# TESTPL.net
KiCad netlist of a schematic drawn in EAGLE
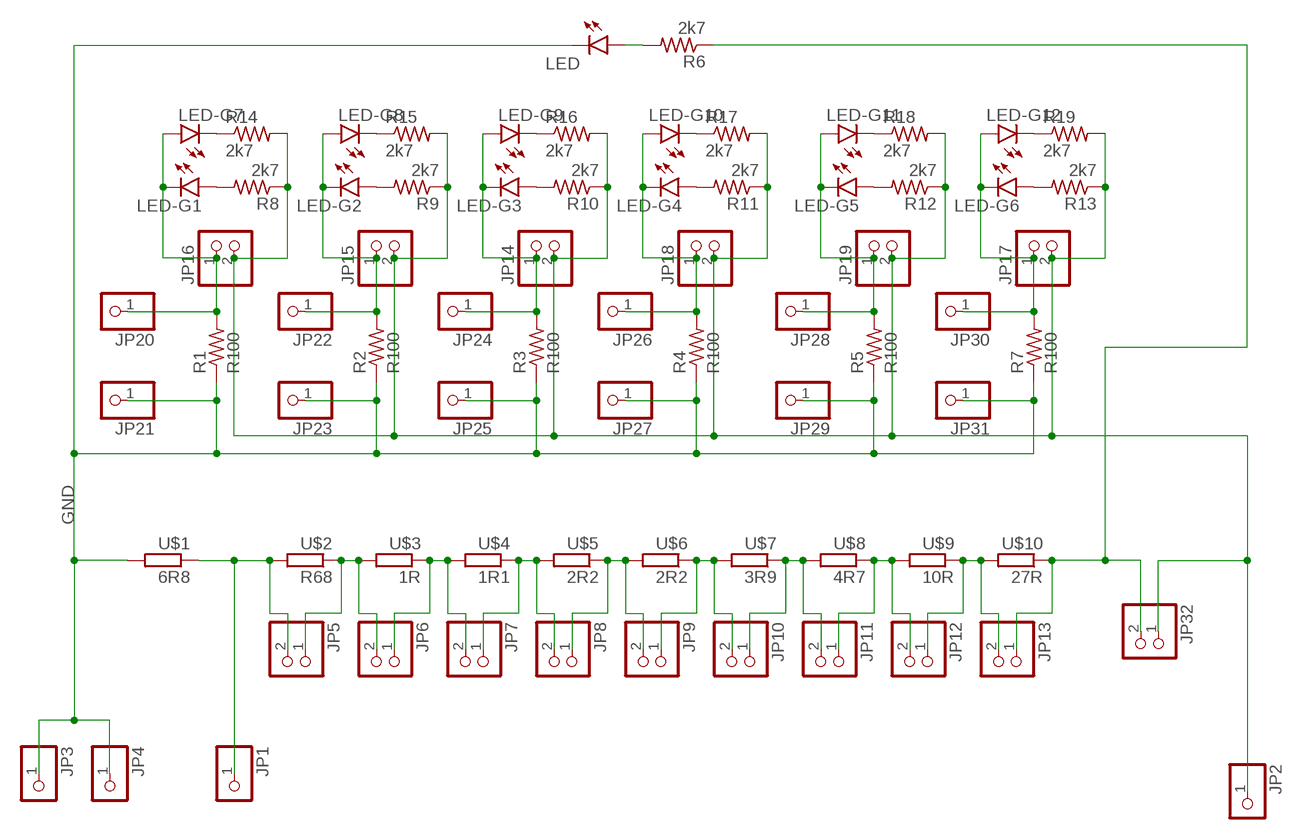
[diagram p0: schematic, sheet 1]

(export (version "E")
  (design (tool "Eeschema 10.0.6"))
  (components
    (comp (ref "JP1")
      (value "PINHD-1X1")
      (footprint "eagle-import:1X01")
      (libsource (lib "eagle-import") (part "PINHD-1X1"))
    )
    (comp (ref "JP2")
      (value "PINHD-1X1")
      (footprint "eagle-import:1X01")
      (libsource (lib "eagle-import") (part "PINHD-1X1"))
    )
    (comp (ref "JP3")
      (value "PINHD-1X1")
      (footprint "eagle-import:1X01")
      (libsource (lib "eagle-import") (part "PINHD-1X1"))
    )
    (comp (ref "JP4")
      (value "PINHD-1X1")
      (footprint "eagle-import:1X01")
      (libsource (lib "eagle-import") (part "PINHD-1X1"))
    )
    (comp (ref "JP5")
      (value "PINHD-1X2")
      (footprint "eagle-import:1X02")
      (libsource (lib "eagle-import") (part "PINHD-1X2"))
    )
    (comp (ref "JP6")
      (value "PINHD-1X2")
      (footprint "eagle-import:1X02")
      (libsource (lib "eagle-import") (part "PINHD-1X2"))
    )
    (comp (ref "JP7")
      (value "PINHD-1X2")
      (footprint "eagle-import:1X02")
      (libsource (lib "eagle-import") (part "PINHD-1X2"))
    )
    (comp (ref "JP8")
      (value "PINHD-1X2")
      (footprint "eagle-import:1X02")
      (libsource (lib "eagle-import") (part "PINHD-1X2"))
    )
    (comp (ref "JP9")
      (value "PINHD-1X2")
      (footprint "eagle-import:1X02")
      (libsource (lib "eagle-import") (part "PINHD-1X2"))
    )
    (comp (ref "JP10")
      (value "PINHD-1X2")
      (footprint "eagle-import:1X02")
      (libsource (lib "eagle-import") (part "PINHD-1X2"))
    )
    (comp (ref "JP11")
      (value "PINHD-1X2")
      (footprint "eagle-import:1X02")
      (libsource (lib "eagle-import") (part "PINHD-1X2"))
    )
    (comp (ref "JP12")
      (value "PINHD-1X2")
      (footprint "eagle-import:1X02")
      (libsource (lib "eagle-import") (part "PINHD-1X2"))
    )
    (comp (ref "JP13")
      (value "PINHD-1X2")
      (footprint "eagle-import:1X02")
      (libsource (lib "eagle-import") (part "PINHD-1X2"))
    )
    (comp (ref "JP14")
      (value "PINHD-1X2")
      (footprint "eagle-import:1X02")
      (libsource (lib "eagle-import") (part "PINHD-1X2"))
    )
    (comp (ref "JP15")
      (value "PINHD-1X2")
      (footprint "eagle-import:1X02")
      (libsource (lib "eagle-import") (part "PINHD-1X2"))
    )
    (comp (ref "JP16")
      (value "PINHD-1X2")
      (footprint "eagle-import:1X02")
      (libsource (lib "eagle-import") (part "PINHD-1X2"))
    )
    (comp (ref "JP17")
      (value "PINHD-1X2")
      (footprint "eagle-import:1X02")
      (libsource (lib "eagle-import") (part "PINHD-1X2"))
    )
    (comp (ref "JP18")
      (value "PINHD-1X2")
      (footprint "eagle-import:1X02")
      (libsource (lib "eagle-import") (part "PINHD-1X2"))
    )
    (comp (ref "JP19")
      (value "PINHD-1X2")
      (footprint "eagle-import:1X02")
      (libsource (lib "eagle-import") (part "PINHD-1X2"))
    )
    (comp (ref "JP20")
      (value "PINHD-1X1")
      (footprint "eagle-import:1X01")
      (libsource (lib "eagle-import") (part "PINHD-1X1"))
    )
    (comp (ref "JP21")
      (value "PINHD-1X1")
      (footprint "eagle-import:1X01")
      (libsource (lib "eagle-import") (part "PINHD-1X1"))
    )
    (comp (ref "JP22")
      (value "PINHD-1X1")
      (footprint "eagle-import:1X01")
      (libsource (lib "eagle-import") (part "PINHD-1X1"))
    )
    (comp (ref "JP23")
      (value "PINHD-1X1")
      (footprint "eagle-import:1X01")
      (libsource (lib "eagle-import") (part "PINHD-1X1"))
    )
    (comp (ref "JP24")
      (value "PINHD-1X1")
      (footprint "eagle-import:1X01")
      (libsource (lib "eagle-import") (part "PINHD-1X1"))
    )
    (comp (ref "JP25")
      (value "PINHD-1X1")
      (footprint "eagle-import:1X01")
      (libsource (lib "eagle-import") (part "PINHD-1X1"))
    )
    (comp (ref "JP26")
      (value "PINHD-1X1")
      (footprint "eagle-import:1X01")
      (libsource (lib "eagle-import") (part "PINHD-1X1"))
    )
    (comp (ref "JP27")
      (value "PINHD-1X1")
      (footprint "eagle-import:1X01")
      (libsource (lib "eagle-import") (part "PINHD-1X1"))
    )
    (comp (ref "JP28")
      (value "PINHD-1X1")
      (footprint "eagle-import:1X01")
      (libsource (lib "eagle-import") (part "PINHD-1X1"))
    )
    (comp (ref "JP29")
      (value "PINHD-1X1")
      (footprint "eagle-import:1X01")
      (libsource (lib "eagle-import") (part "PINHD-1X1"))
    )
    (comp (ref "JP30")
      (value "PINHD-1X1")
      (footprint "eagle-import:1X01")
      (libsource (lib "eagle-import") (part "PINHD-1X1"))
    )
    (comp (ref "JP31")
      (value "PINHD-1X1")
      (footprint "eagle-import:1X01")
      (libsource (lib "eagle-import") (part "PINHD-1X1"))
    )
    (comp (ref "JP32")
      (value "PINHD-1X2")
      (footprint "eagle-import:1X02")
      (libsource (lib "eagle-import") (part "PINHD-1X2"))
    )
    (comp (ref "LED")
      (value "LEDCHIPLED_0603")
      (footprint "eagle-import:CHIPLED_0603")
      (libsource (lib "eagle-import") (part "LEDCHIPLED_0603"))
    )
    (comp (ref "LED-G1")
      (value "LEDCHIPLED_0603")
      (footprint "eagle-import:CHIPLED_0603")
      (libsource (lib "eagle-import") (part "LEDCHIPLED_0603"))
    )
    (comp (ref "LED-G2")
      (value "LEDCHIPLED_0603")
      (footprint "eagle-import:CHIPLED_0603")
      (libsource (lib "eagle-import") (part "LEDCHIPLED_0603"))
    )
    (comp (ref "LED-G3")
      (value "LEDCHIPLED_0603")
      (footprint "eagle-import:CHIPLED_0603")
      (libsource (lib "eagle-import") (part "LEDCHIPLED_0603"))
    )
    (comp (ref "LED-G4")
      (value "LEDCHIPLED_0603")
      (footprint "eagle-import:CHIPLED_0603")
      (libsource (lib "eagle-import") (part "LEDCHIPLED_0603"))
    )
    (comp (ref "LED-G5")
      (value "LEDCHIPLED_0603")
      (footprint "eagle-import:CHIPLED_0603")
      (libsource (lib "eagle-import") (part "LEDCHIPLED_0603"))
    )
    (comp (ref "LED-G6")
      (value "LEDCHIPLED_0603")
      (footprint "eagle-import:CHIPLED_0603")
      (libsource (lib "eagle-import") (part "LEDCHIPLED_0603"))
    )
    (comp (ref "LED-G7")
      (value "LEDCHIPLED_0603")
      (footprint "eagle-import:CHIPLED_0603")
      (libsource (lib "eagle-import") (part "LEDCHIPLED_0603"))
    )
    (comp (ref "LED-G8")
      (value "LEDCHIPLED_0603")
      (footprint "eagle-import:CHIPLED_0603")
      (libsource (lib "eagle-import") (part "LEDCHIPLED_0603"))
    )
    (comp (ref "LED-G9")
      (value "LEDCHIPLED_0603")
      (footprint "eagle-import:CHIPLED_0603")
      (libsource (lib "eagle-import") (part "LEDCHIPLED_0603"))
    )
    (comp (ref "LED-G10")
      (value "LEDCHIPLED_0603")
      (footprint "eagle-import:CHIPLED_0603")
      (libsource (lib "eagle-import") (part "LEDCHIPLED_0603"))
    )
    (comp (ref "LED-G11")
      (value "LEDCHIPLED_0603")
      (footprint "eagle-import:CHIPLED_0603")
      (libsource (lib "eagle-import") (part "LEDCHIPLED_0603"))
    )
    (comp (ref "LED-G12")
      (value "LEDCHIPLED_0603")
      (footprint "eagle-import:CHIPLED_0603")
      (libsource (lib "eagle-import") (part "LEDCHIPLED_0603"))
    )
    (comp (ref "R1")
      (value "R100")
      (footprint "eagle-import:R2512")
      (libsource (lib "eagle-import") (part "R-US_R2512"))
    )
    (comp (ref "R2")
      (value "R100")
      (footprint "eagle-import:R2512")
      (libsource (lib "eagle-import") (part "R-US_R2512"))
    )
    (comp (ref "R3")
      (value "R100")
      (footprint "eagle-import:R2512")
      (libsource (lib "eagle-import") (part "R-US_R2512"))
    )
    (comp (ref "R4")
      (value "R100")
      (footprint "eagle-import:R2512")
      (libsource (lib "eagle-import") (part "R-US_R2512"))
    )
    (comp (ref "R5")
      (value "R100")
      (footprint "eagle-import:R2512")
      (libsource (lib "eagle-import") (part "R-US_R2512"))
    )
    (comp (ref "R6")
      (value "2k7")
      (footprint "eagle-import:R0603")
      (libsource (lib "eagle-import") (part "resistor_348_R-US_R0603"))
    )
    (comp (ref "R7")
      (value "R100")
      (footprint "eagle-import:R2512")
      (libsource (lib "eagle-import") (part "R-US_R2512"))
    )
    (comp (ref "R8")
      (value "2k7")
      (footprint "eagle-import:R0603")
      (libsource (lib "eagle-import") (part "resistor_348_R-US_R0603"))
    )
    (comp (ref "R9")
      (value "2k7")
      (footprint "eagle-import:R0603")
      (libsource (lib "eagle-import") (part "resistor_348_R-US_R0603"))
    )
    (comp (ref "R10")
      (value "2k7")
      (footprint "eagle-import:R0603")
      (libsource (lib "eagle-import") (part "resistor_348_R-US_R0603"))
    )
    (comp (ref "R11")
      (value "2k7")
      (footprint "eagle-import:R0603")
      (libsource (lib "eagle-import") (part "resistor_348_R-US_R0603"))
    )
    (comp (ref "R12")
      (value "2k7")
      (footprint "eagle-import:R0603")
      (libsource (lib "eagle-import") (part "resistor_348_R-US_R0603"))
    )
    (comp (ref "R13")
      (value "2k7")
      (footprint "eagle-import:R0603")
      (libsource (lib "eagle-import") (part "resistor_348_R-US_R0603"))
    )
    (comp (ref "R14")
      (value "2k7")
      (footprint "eagle-import:R0603")
      (libsource (lib "eagle-import") (part "resistor_348_R-US_R0603"))
    )
    (comp (ref "R15")
      (value "2k7")
      (footprint "eagle-import:R0603")
      (libsource (lib "eagle-import") (part "resistor_348_R-US_R0603"))
    )
    (comp (ref "R16")
      (value "2k7")
      (footprint "eagle-import:R0603")
      (libsource (lib "eagle-import") (part "resistor_348_R-US_R0603"))
    )
    (comp (ref "R17")
      (value "2k7")
      (footprint "eagle-import:R0603")
      (libsource (lib "eagle-import") (part "resistor_348_R-US_R0603"))
    )
    (comp (ref "R18")
      (value "2k7")
      (footprint "eagle-import:R0603")
      (libsource (lib "eagle-import") (part "resistor_348_R-US_R0603"))
    )
    (comp (ref "R19")
      (value "2k7")
      (footprint "eagle-import:R0603")
      (libsource (lib "eagle-import") (part "resistor_348_R-US_R0603"))
    )
    (comp (ref "U$1")
      (value "6R8")
      (footprint "eagle-import:SQP")
      (libsource (lib "eagle-import") (part "SQP"))
    )
    (comp (ref "U$2")
      (value "R68")
      (footprint "eagle-import:SQP")
      (libsource (lib "eagle-import") (part "SQP"))
    )
    (comp (ref "U$3")
      (value "1R")
      (footprint "eagle-import:SQP")
      (libsource (lib "eagle-import") (part "SQP"))
    )
    (comp (ref "U$4")
      (value "1R1")
      (footprint "eagle-import:SQP")
      (libsource (lib "eagle-import") (part "SQP"))
    )
    (comp (ref "U$5")
      (value "2R2")
      (footprint "eagle-import:SQP")
      (libsource (lib "eagle-import") (part "SQP"))
    )
    (comp (ref "U$6")
      (value "2R2")
      (footprint "eagle-import:SQP")
      (libsource (lib "eagle-import") (part "SQP"))
    )
    (comp (ref "U$7")
      (value "3R9")
      (footprint "eagle-import:SQP")
      (libsource (lib "eagle-import") (part "SQP"))
    )
    (comp (ref "U$8")
      (value "4R7")
      (footprint "eagle-import:SQP")
      (libsource (lib "eagle-import") (part "SQP"))
    )
    (comp (ref "U$9")
      (value "10R")
      (footprint "eagle-import:SQP")
      (libsource (lib "eagle-import") (part "SQP"))
    )
    (comp (ref "U$10")
      (value "27R")
      (footprint "eagle-import:SQP")
      (libsource (lib "eagle-import") (part "SQP"))
    )
  )
  (nets
    (net (code "1") (name "/GND") (class "Default")
      (node (ref "JP21") (pin "1") (pinfunction "1_1") (pintype "passive"))
      (node (ref "JP23") (pin "1") (pinfunction "1_1") (pintype "passive"))
      (node (ref "JP25") (pin "1") (pinfunction "1_1") (pintype "passive"))
      (node (ref "JP27") (pin "1") (pinfunction "1_1") (pintype "passive"))
      (node (ref "JP29") (pin "1") (pinfunction "1_1") (pintype "passive"))
      (node (ref "JP3") (pin "1") (pinfunction "1_1") (pintype "passive"))
      (node (ref "JP31") (pin "1") (pinfunction "1_1") (pintype "passive"))
      (node (ref "JP4") (pin "1") (pinfunction "1_1") (pintype "passive"))
      (node (ref "LED") (pin "C") (pinfunction "C_C") (pintype "passive"))
      (node (ref "R1") (pin "1") (pinfunction "1_1") (pintype "passive"))
      (node (ref "R2") (pin "1") (pinfunction "1_1") (pintype "passive"))
      (node (ref "R3") (pin "1") (pinfunction "1_1") (pintype "passive"))
      (node (ref "R4") (pin "1") (pinfunction "1_1") (pintype "passive"))
      (node (ref "R5") (pin "1") (pinfunction "1_1") (pintype "passive"))
      (node (ref "R7") (pin "1") (pinfunction "1_1") (pintype "passive"))
      (node (ref "U$1") (pin "P$2") (pinfunction "2_P$2") (pintype "passive"))
    )
    (net (code "2") (name "Net-(JP14-Pad1)") (class "Default")
      (node (ref "JP14") (pin "1") (pinfunction "1_1") (pintype "passive"))
      (node (ref "JP24") (pin "1") (pinfunction "1_1") (pintype "passive"))
      (node (ref "LED-G3") (pin "C") (pinfunction "C_C") (pintype "passive"))
      (node (ref "LED-G9") (pin "A") (pinfunction "A_A") (pintype "passive"))
      (node (ref "R3") (pin "2") (pinfunction "2_2") (pintype "passive"))
    )
    (net (code "3") (name "Net-(JP14-Pad2)") (class "Default")
      (node (ref "JP14") (pin "2") (pinfunction "2_2") (pintype "passive"))
      (node (ref "JP15") (pin "2") (pinfunction "2_2") (pintype "passive"))
      (node (ref "JP16") (pin "2") (pinfunction "2_2") (pintype "passive"))
      (node (ref "JP17") (pin "2") (pinfunction "2_2") (pintype "passive"))
      (node (ref "JP18") (pin "2") (pinfunction "2_2") (pintype "passive"))
      (node (ref "JP19") (pin "2") (pinfunction "2_2") (pintype "passive"))
      (node (ref "JP2") (pin "1") (pinfunction "1_1") (pintype "passive"))
      (node (ref "JP32") (pin "1") (pinfunction "1_1") (pintype "passive"))
      (node (ref "R10") (pin "1") (pinfunction "1_1") (pintype "passive"))
      (node (ref "R11") (pin "1") (pinfunction "1_1") (pintype "passive"))
      (node (ref "R12") (pin "1") (pinfunction "1_1") (pintype "passive"))
      (node (ref "R13") (pin "1") (pinfunction "1_1") (pintype "passive"))
      (node (ref "R14") (pin "2") (pinfunction "2_2") (pintype "passive"))
      (node (ref "R15") (pin "2") (pinfunction "2_2") (pintype "passive"))
      (node (ref "R16") (pin "2") (pinfunction "2_2") (pintype "passive"))
      (node (ref "R17") (pin "2") (pinfunction "2_2") (pintype "passive"))
      (node (ref "R18") (pin "2") (pinfunction "2_2") (pintype "passive"))
      (node (ref "R19") (pin "2") (pinfunction "2_2") (pintype "passive"))
      (node (ref "R8") (pin "1") (pinfunction "1_1") (pintype "passive"))
      (node (ref "R9") (pin "1") (pinfunction "1_1") (pintype "passive"))
    )
    (net (code "4") (name "Net-(JP15-Pad1)") (class "Default")
      (node (ref "JP15") (pin "1") (pinfunction "1_1") (pintype "passive"))
      (node (ref "JP22") (pin "1") (pinfunction "1_1") (pintype "passive"))
      (node (ref "LED-G2") (pin "C") (pinfunction "C_C") (pintype "passive"))
      (node (ref "LED-G8") (pin "A") (pinfunction "A_A") (pintype "passive"))
      (node (ref "R2") (pin "2") (pinfunction "2_2") (pintype "passive"))
    )
    (net (code "5") (name "Net-(JP16-Pad1)") (class "Default")
      (node (ref "JP16") (pin "1") (pinfunction "1_1") (pintype "passive"))
      (node (ref "JP20") (pin "1") (pinfunction "1_1") (pintype "passive"))
      (node (ref "LED-G1") (pin "C") (pinfunction "C_C") (pintype "passive"))
      (node (ref "LED-G7") (pin "A") (pinfunction "A_A") (pintype "passive"))
      (node (ref "R1") (pin "2") (pinfunction "2_2") (pintype "passive"))
    )
    (net (code "6") (name "Net-(JP17-Pad1)") (class "Default")
      (node (ref "JP17") (pin "1") (pinfunction "1_1") (pintype "passive"))
      (node (ref "JP30") (pin "1") (pinfunction "1_1") (pintype "passive"))
      (node (ref "LED-G12") (pin "A") (pinfunction "A_A") (pintype "passive"))
      (node (ref "LED-G6") (pin "C") (pinfunction "C_C") (pintype "passive"))
      (node (ref "R7") (pin "2") (pinfunction "2_2") (pintype "passive"))
    )
    (net (code "7") (name "Net-(JP18-Pad1)") (class "Default")
      (node (ref "JP18") (pin "1") (pinfunction "1_1") (pintype "passive"))
      (node (ref "JP26") (pin "1") (pinfunction "1_1") (pintype "passive"))
      (node (ref "LED-G10") (pin "A") (pinfunction "A_A") (pintype "passive"))
      (node (ref "LED-G4") (pin "C") (pinfunction "C_C") (pintype "passive"))
      (node (ref "R4") (pin "2") (pinfunction "2_2") (pintype "passive"))
    )
    (net (code "8") (name "Net-(JP19-Pad1)") (class "Default")
      (node (ref "JP19") (pin "1") (pinfunction "1_1") (pintype "passive"))
      (node (ref "JP28") (pin "1") (pinfunction "1_1") (pintype "passive"))
      (node (ref "LED-G11") (pin "A") (pinfunction "A_A") (pintype "passive"))
      (node (ref "LED-G5") (pin "C") (pinfunction "C_C") (pintype "passive"))
      (node (ref "R5") (pin "2") (pinfunction "2_2") (pintype "passive"))
    )
    (net (code "9") (name "Net-(LED-G1-PadA)") (class "Default")
      (node (ref "LED-G1") (pin "A") (pinfunction "A_A") (pintype "passive"))
      (node (ref "R8") (pin "2") (pinfunction "2_2") (pintype "passive"))
    )
    (net (code "10") (name "Net-(LED-G2-PadA)") (class "Default")
      (node (ref "LED-G2") (pin "A") (pinfunction "A_A") (pintype "passive"))
      (node (ref "R9") (pin "2") (pinfunction "2_2") (pintype "passive"))
    )
    (net (code "11") (name "Net-(LED-G3-PadA)") (class "Default")
      (node (ref "LED-G3") (pin "A") (pinfunction "A_A") (pintype "passive"))
      (node (ref "R10") (pin "2") (pinfunction "2_2") (pintype "passive"))
    )
    (net (code "12") (name "Net-(LED-G4-PadA)") (class "Default")
      (node (ref "LED-G4") (pin "A") (pinfunction "A_A") (pintype "passive"))
      (node (ref "R11") (pin "2") (pinfunction "2_2") (pintype "passive"))
    )
    (net (code "13") (name "Net-(LED-G5-PadA)") (class "Default")
      (node (ref "LED-G5") (pin "A") (pinfunction "A_A") (pintype "passive"))
      (node (ref "R12") (pin "2") (pinfunction "2_2") (pintype "passive"))
    )
    (net (code "14") (name "Net-(LED-G6-PadA)") (class "Default")
      (node (ref "LED-G6") (pin "A") (pinfunction "A_A") (pintype "passive"))
      (node (ref "R13") (pin "2") (pinfunction "2_2") (pintype "passive"))
    )
    (net (code "15") (name "Net-(LED-G7-PadC)") (class "Default")
      (node (ref "LED-G7") (pin "C") (pinfunction "C_C") (pintype "passive"))
      (node (ref "R14") (pin "1") (pinfunction "1_1") (pintype "passive"))
    )
    (net (code "16") (name "Net-(LED-G8-PadC)") (class "Default")
      (node (ref "LED-G8") (pin "C") (pinfunction "C_C") (pintype "passive"))
      (node (ref "R15") (pin "1") (pinfunction "1_1") (pintype "passive"))
    )
    (net (code "17") (name "Net-(LED-G9-PadC)") (class "Default")
      (node (ref "LED-G9") (pin "C") (pinfunction "C_C") (pintype "passive"))
      (node (ref "R16") (pin "1") (pinfunction "1_1") (pintype "passive"))
    )
    (net (code "18") (name "Net-(LED-G10-PadC)") (class "Default")
      (node (ref "LED-G10") (pin "C") (pinfunction "C_C") (pintype "passive"))
      (node (ref "R17") (pin "1") (pinfunction "1_1") (pintype "passive"))
    )
    (net (code "19") (name "Net-(LED-G11-PadC)") (class "Default")
      (node (ref "LED-G11") (pin "C") (pinfunction "C_C") (pintype "passive"))
      (node (ref "R18") (pin "1") (pinfunction "1_1") (pintype "passive"))
    )
    (net (code "20") (name "Net-(LED-G12-PadC)") (class "Default")
      (node (ref "LED-G12") (pin "C") (pinfunction "C_C") (pintype "passive"))
      (node (ref "R19") (pin "1") (pinfunction "1_1") (pintype "passive"))
    )
    (net (code "21") (name "Net-(LED-PadA)") (class "Default")
      (node (ref "LED") (pin "A") (pinfunction "A_A") (pintype "passive"))
      (node (ref "R6") (pin "2") (pinfunction "2_2") (pintype "passive"))
    )
    (net (code "22") (name "Net-(U$1-1)") (class "Default")
      (node (ref "JP1") (pin "1") (pinfunction "1_1") (pintype "passive"))
      (node (ref "JP5") (pin "2") (pinfunction "2_2") (pintype "passive"))
      (node (ref "U$1") (pin "P$1") (pinfunction "1_P$1") (pintype "passive"))
      (node (ref "U$2") (pin "P$2") (pinfunction "2_P$2") (pintype "passive"))
    )
    (net (code "23") (name "Net-(U$2-1)") (class "Default")
      (node (ref "JP5") (pin "1") (pinfunction "1_1") (pintype "passive"))
      (node (ref "JP6") (pin "2") (pinfunction "2_2") (pintype "passive"))
      (node (ref "U$2") (pin "P$1") (pinfunction "1_P$1") (pintype "passive"))
      (node (ref "U$3") (pin "P$2") (pinfunction "2_P$2") (pintype "passive"))
    )
    (net (code "24") (name "Net-(U$3-1)") (class "Default")
      (node (ref "JP6") (pin "1") (pinfunction "1_1") (pintype "passive"))
      (node (ref "JP7") (pin "2") (pinfunction "2_2") (pintype "passive"))
      (node (ref "U$3") (pin "P$1") (pinfunction "1_P$1") (pintype "passive"))
      (node (ref "U$4") (pin "P$2") (pinfunction "2_P$2") (pintype "passive"))
    )
    (net (code "25") (name "Net-(U$4-1)") (class "Default")
      (node (ref "JP7") (pin "1") (pinfunction "1_1") (pintype "passive"))
      (node (ref "JP8") (pin "2") (pinfunction "2_2") (pintype "passive"))
      (node (ref "U$4") (pin "P$1") (pinfunction "1_P$1") (pintype "passive"))
      (node (ref "U$5") (pin "P$2") (pinfunction "2_P$2") (pintype "passive"))
    )
    (net (code "26") (name "Net-(U$5-1)") (class "Default")
      (node (ref "JP8") (pin "1") (pinfunction "1_1") (pintype "passive"))
      (node (ref "JP9") (pin "2") (pinfunction "2_2") (pintype "passive"))
      (node (ref "U$5") (pin "P$1") (pinfunction "1_P$1") (pintype "passive"))
      (node (ref "U$6") (pin "P$2") (pinfunction "2_P$2") (pintype "passive"))
    )
    (net (code "27") (name "Net-(U$6-1)") (class "Default")
      (node (ref "JP10") (pin "2") (pinfunction "2_2") (pintype "passive"))
      (node (ref "JP9") (pin "1") (pinfunction "1_1") (pintype "passive"))
      (node (ref "U$6") (pin "P$1") (pinfunction "1_P$1") (pintype "passive"))
      (node (ref "U$7") (pin "P$2") (pinfunction "2_P$2") (pintype "passive"))
    )
    (net (code "28") (name "Net-(U$7-1)") (class "Default")
      (node (ref "JP10") (pin "1") (pinfunction "1_1") (pintype "passive"))
      (node (ref "JP11") (pin "2") (pinfunction "2_2") (pintype "passive"))
      (node (ref "U$7") (pin "P$1") (pinfunction "1_P$1") (pintype "passive"))
      (node (ref "U$8") (pin "P$2") (pinfunction "2_P$2") (pintype "passive"))
    )
    (net (code "29") (name "Net-(U$8-1)") (class "Default")
      (node (ref "JP11") (pin "1") (pinfunction "1_1") (pintype "passive"))
      (node (ref "JP12") (pin "2") (pinfunction "2_2") (pintype "passive"))
      (node (ref "U$8") (pin "P$1") (pinfunction "1_P$1") (pintype "passive"))
      (node (ref "U$9") (pin "P$2") (pinfunction "2_P$2") (pintype "passive"))
    )
    (net (code "30") (name "Net-(U$10-1)") (class "Default")
      (node (ref "JP13") (pin "1") (pinfunction "1_1") (pintype "passive"))
      (node (ref "JP32") (pin "2") (pinfunction "2_2") (pintype "passive"))
      (node (ref "R6") (pin "1") (pinfunction "1_1") (pintype "passive"))
      (node (ref "U$10") (pin "P$1") (pinfunction "1_P$1") (pintype "passive"))
    )
    (net (code "31") (name "Net-(U$10-2)") (class "Default")
      (node (ref "JP12") (pin "1") (pinfunction "1_1") (pintype "passive"))
      (node (ref "JP13") (pin "2") (pinfunction "2_2") (pintype "passive"))
      (node (ref "U$10") (pin "P$2") (pinfunction "2_P$2") (pintype "passive"))
      (node (ref "U$9") (pin "P$1") (pinfunction "1_P$1") (pintype "passive"))
    )
  )
)
